# Motor_Measure.net
KiCad netlist of a schematic drawn in Altium Designer
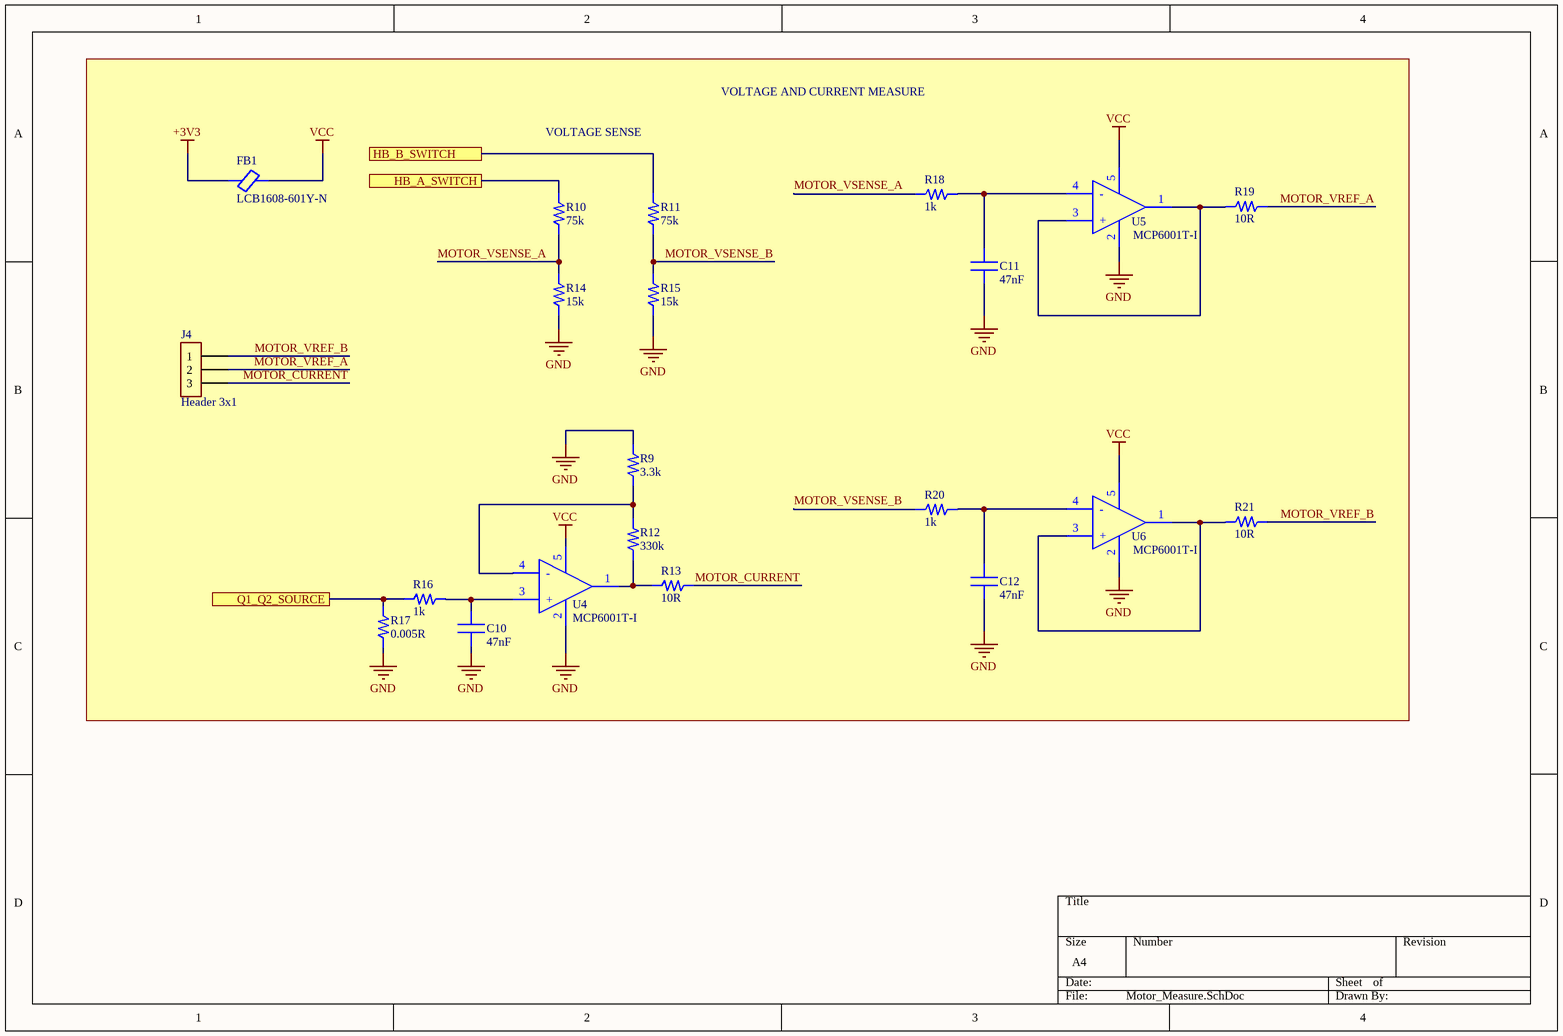
[diagram p0: Motor_Measure.SchDoc]

(export (version "E")
  (design (tool "Eeschema 10.0.6"))
  (components
    (comp (ref "C10")
      (value "47nF")
      (footprint "CAPC2012X145N 0805")
      (description "CL21B473KBCNNNC")
      (fields (field (name "TOLERANCE") "±10 %") (field (name "MANUFACTURER") "SAMSUNG"))
      (libsource (lib "Chicken_Coop_Door_Main_Board_V3") (part "CAP 0805 47nF CL21B473KBCNNNC"))
    )
    (comp (ref "C11")
      (value "47nF")
      (footprint "CAPC2012X145N 0805")
      (description "CL21B473KBCNNNC")
      (fields (field (name "TOLERANCE") "±10 %") (field (name "MANUFACTURER") "SAMSUNG"))
      (libsource (lib "Chicken_Coop_Door_Main_Board_V3") (part "CAP 0805 47nF CL21B473KBCNNNC"))
    )
    (comp (ref "C12")
      (value "47nF")
      (footprint "CAPC2012X145N 0805")
      (description "CL21B473KBCNNNC")
      (fields (field (name "TOLERANCE") "±10 %") (field (name "MANUFACTURER") "SAMSUNG"))
      (libsource (lib "Chicken_Coop_Door_Main_Board_V3") (part "CAP 0805 47nF CL21B473KBCNNNC"))
    )
    (comp (ref "FB1")
      (value "LCB1608-601Y-N")
      (footprint "MPZ1608S601ATA00 0603 1608X95N")
      (description "600 Ohms @ 100 MHz 1 Power Line Ferrite Bead 0603 (1608 Metric) 1A 200mOhm")
      (fields (field (name "TOLERANCE") "±25 %") (field (name "MANUFACTURER") "CORE MASTER"))
      (libsource (lib "Chicken_Coop_Door_Main_Board_V3") (part "Ferrite Bead LCB1608-601Y-N"))
    )
    (comp (ref "J4")
      (value "Header 3x1")
      (footprint "JST_B3B-PH-K-S 1x3 Header")
      (description "CON.T.B.2.00MM 3P 180C MALE CONNFLY")
      (fields (field (name "MANUFACTURER") "CONNFLY"))
      (libsource (lib "Chicken_Coop_Door_Main_Board_V3") (part "Header 3x1 DS1066-3MVW6X"))
    )
    (comp (ref "R9")
      (value "3.3k")
      (footprint "RES 0805 YAGEO C2012X60N")
      (description "RES.(2012) 0805 3.3K Ohms 1% 1/8W-S 100PPM")
      (fields (field (name "POWER") "1/8W") (field (name "TOLERANCE") "±1 %"))
      (libsource (lib "Chicken_Coop_Door_Main_Board_V3") (part "RES 0805 3.3k Ohms 0805S8F3301TDE"))
    )
    (comp (ref "R10")
      (value "75k")
      (footprint "RES 0805 YAGEO C2012X60N")
      (description "RES.(2012) 0805 75K Ohms 1% 1/8W-S 100PPM")
      (fields (field (name "POWER") "1/8W") (field (name "TOLERANCE") "±1 %"))
      (libsource (lib "Chicken_Coop_Door_Main_Board_V3") (part "RES 0805 75 kOhms 0805S8F7502T5E"))
    )
    (comp (ref "R11")
      (value "75k")
      (footprint "RES 0805 YAGEO C2012X60N")
      (description "RES.(2012) 0805 75K Ohms 1% 1/8W-S 100PPM")
      (fields (field (name "POWER") "1/8W") (field (name "TOLERANCE") "±1 %"))
      (libsource (lib "Chicken_Coop_Door_Main_Board_V3") (part "RES 0805 75 kOhms 0805S8F7502T5E"))
    )
    (comp (ref "R12")
      (value "330k")
      (footprint "RES 0603 ROYALOHM")
      (description "RES.(1608) 0603 330K Ohms 1% 1/10W-S 100PPM")
      (fields (field (name "TOLERANCE") "±5 %") (field (name "MANUFACTURER") "ROYALOHM"))
      (libsource (lib "Chicken_Coop_Door_Main_Board_V3") (part "RES 0603 330k 0603SAF3303T5E"))
    )
    (comp (ref "R13")
      (value "10R")
      (footprint "RES 0805 YAGEO C2012X60N")
      (description "RES.(2012) 0805 10 Ohms 5% 1/8W-S 400PPM")
      (fields (field (name "POWER") "1/8W") (field (name "TOLERANCE") "±1 %"))
      (libsource (lib "Chicken_Coop_Door_Main_Board_V3") (part "RES 0805 10 Ohms 0805S8J0100T5E"))
    )
    (comp (ref "R14")
      (value "15k")
      (footprint "RES 0805 YAGEO C2012X60N")
      (description "RES.(2012) 0805 15K Ohms 0.5% 1/8W 25PPM")
      (fields (field (name "POWER") "1/8W") (field (name "TOLERANCE") "±1 %"))
      (libsource (lib "Chicken_Coop_Door_Main_Board_V3") (part "RES 0805 15 kOhms TC0525D1502T5G"))
    )
    (comp (ref "R15")
      (value "15k")
      (footprint "RES 0805 YAGEO C2012X60N")
      (description "RES.(2012) 0805 15K Ohms 0.5% 1/8W 25PPM")
      (fields (field (name "POWER") "1/8W") (field (name "TOLERANCE") "±1 %"))
      (libsource (lib "Chicken_Coop_Door_Main_Board_V3") (part "RES 0805 15 kOhms TC0525D1502T5G"))
    )
    (comp (ref "R16")
      (value "1k")
      (footprint "RES 0805 YAGEO C2012X60N")
      (description "RES.(2012) 0805 1K Ohms 1% 1/8W-S 100PPM")
      (fields (field (name "POWER") "1/8W") (field (name "TOLERANCE") "±1 %"))
      (libsource (lib "Chicken_Coop_Door_Main_Board_V3") (part "RES 0805 1k Ohms 0805S8F1001TDE"))
    )
    (comp (ref "R17")
      (value "0.005R")
      (footprint "RES 1206 YAGEO")
      (description "RES.(3216) 1206 5m Ohms 1% 1/4W 100PPM AEC-Q200 SM")
      (fields (field (name "POWER") "1/4W") (field (name "TOLERANCE") "±1 %"))
      (libsource (lib "Chicken_Coop_Door_Main_Board_V3") (part "RES 1206 5 mOhms PE1206FRF070R005L"))
    )
    (comp (ref "R18")
      (value "1k")
      (footprint "RES 0805 YAGEO C2012X60N")
      (description "RES.(2012) 0805 1K Ohms 1% 1/8W-S 100PPM")
      (fields (field (name "POWER") "1/8W") (field (name "TOLERANCE") "±1 %"))
      (libsource (lib "Chicken_Coop_Door_Main_Board_V3") (part "RES 0805 1k Ohms 0805S8F1001TDE"))
    )
    (comp (ref "R19")
      (value "10R")
      (footprint "RES 0805 YAGEO C2012X60N")
      (description "RES.(2012) 0805 10 Ohms 5% 1/8W-S 400PPM")
      (fields (field (name "POWER") "1/8W") (field (name "TOLERANCE") "±1 %"))
      (libsource (lib "Chicken_Coop_Door_Main_Board_V3") (part "RES 0805 10 Ohms 0805S8J0100T5E"))
    )
    (comp (ref "R20")
      (value "1k")
      (footprint "RES 0805 YAGEO C2012X60N")
      (description "RES.(2012) 0805 1K Ohms 1% 1/8W-S 100PPM")
      (fields (field (name "POWER") "1/8W") (field (name "TOLERANCE") "±1 %"))
      (libsource (lib "Chicken_Coop_Door_Main_Board_V3") (part "RES 0805 1k Ohms 0805S8F1001TDE"))
    )
    (comp (ref "R21")
      (value "10R")
      (footprint "RES 0805 YAGEO C2012X60N")
      (description "RES.(2012) 0805 10 Ohms 5% 1/8W-S 400PPM")
      (fields (field (name "POWER") "1/8W") (field (name "TOLERANCE") "±1 %"))
      (libsource (lib "Chicken_Coop_Door_Main_Board_V3") (part "RES 0805 10 Ohms 0805S8J0100T5E"))
    )
    (comp (ref "U4")
      (value "MCP6001T-I")
      (footprint "MCP6001T-I/OT OPAMP SOT-23-5")
      (description "Standard (General Purpose) Amplifier 1 Circuit Rail-to-Rail SOT-23-5")
      (fields (field (name "MANUFACTURER") "Microchip Technology"))
      (libsource (lib "Chicken_Coop_Door_Main_Board_V3") (part "MCP6001T-I/OT OP-AMP 1 CH LOW POWER"))
    )
    (comp (ref "U5")
      (value "MCP6001T-I")
      (footprint "MCP6001T-I/OT OPAMP SOT-23-5")
      (description "Standard (General Purpose) Amplifier 1 Circuit Rail-to-Rail SOT-23-5")
      (fields (field (name "MANUFACTURER") "Microchip Technology"))
      (libsource (lib "Chicken_Coop_Door_Main_Board_V3") (part "MCP6001T-I/OT OP-AMP 1 CH LOW POWER"))
    )
    (comp (ref "U6")
      (value "MCP6001T-I")
      (footprint "MCP6001T-I/OT OPAMP SOT-23-5")
      (description "Standard (General Purpose) Amplifier 1 Circuit Rail-to-Rail SOT-23-5")
      (fields (field (name "MANUFACTURER") "Microchip Technology"))
      (libsource (lib "Chicken_Coop_Door_Main_Board_V3") (part "MCP6001T-I/OT OP-AMP 1 CH LOW POWER"))
    )
  )
  (nets
    (net (code "1") (name "+3V3") (class "Default")
      (node (ref "FB1") (pin "1") (pinfunction "1_1") (pintype "passive"))
    )
    (net (code "2") (name "/HB_A_SWITCH") (class "Default")
      (node (ref "R10") (pin "2") (pinfunction "2_2") (pintype "passive"))
    )
    (net (code "3") (name "/HB_B_SWITCH") (class "Default")
      (node (ref "R11") (pin "2") (pinfunction "2_2") (pintype "passive"))
    )
    (net (code "4") (name "/MOTOR_CURRENT") (class "Default")
      (node (ref "J4") (pin "3") (pinfunction "3_3") (pintype "passive"))
      (node (ref "R13") (pin "2") (pinfunction "2_2") (pintype "passive"))
    )
    (net (code "5") (name "/MOTOR_VREF_A") (class "Default")
      (node (ref "J4") (pin "2") (pinfunction "2_2") (pintype "passive"))
      (node (ref "R19") (pin "2") (pinfunction "2_2") (pintype "passive"))
    )
    (net (code "6") (name "/MOTOR_VREF_B") (class "Default")
      (node (ref "J4") (pin "1") (pinfunction "1_1") (pintype "passive"))
      (node (ref "R21") (pin "2") (pinfunction "2_2") (pintype "passive"))
    )
    (net (code "7") (name "/MOTOR_VSENSE_A") (class "Default")
      (node (ref "R10") (pin "1") (pinfunction "1_1") (pintype "passive"))
      (node (ref "R14") (pin "2") (pinfunction "2_2") (pintype "passive"))
      (node (ref "R18") (pin "1") (pinfunction "1_1") (pintype "passive"))
    )
    (net (code "8") (name "/MOTOR_VSENSE_B") (class "Default")
      (node (ref "R11") (pin "1") (pinfunction "1_1") (pintype "passive"))
      (node (ref "R15") (pin "2") (pinfunction "2_2") (pintype "passive"))
      (node (ref "R20") (pin "1") (pinfunction "1_1") (pintype "passive"))
    )
    (net (code "9") (name "/Q1_Q2_SOURCE") (class "Default")
      (node (ref "R16") (pin "1") (pinfunction "1_1") (pintype "passive"))
      (node (ref "R17") (pin "2") (pinfunction "2_2") (pintype "passive"))
    )
    (net (code "10") (name "GND") (class "Default")
      (node (ref "C10") (pin "1") (pinfunction "1_1") (pintype "passive"))
      (node (ref "C11") (pin "1") (pinfunction "1_1") (pintype "passive"))
      (node (ref "C12") (pin "1") (pinfunction "1_1") (pintype "passive"))
      (node (ref "R14") (pin "1") (pinfunction "1_1") (pintype "passive"))
      (node (ref "R15") (pin "1") (pinfunction "1_1") (pintype "passive"))
      (node (ref "R17") (pin "1") (pinfunction "1_1") (pintype "passive"))
      (node (ref "R9") (pin "2") (pinfunction "2_2") (pintype "passive"))
      (node (ref "U4") (pin "2") (pinfunction "VSS_2") (pintype "passive"))
      (node (ref "U5") (pin "2") (pinfunction "VSS_2") (pintype "passive"))
      (node (ref "U6") (pin "2") (pinfunction "VSS_2") (pintype "passive"))
    )
    (net (code "11") (name "Net-(U4-+)") (class "Default")
      (node (ref "C10") (pin "2") (pinfunction "2_2") (pintype "passive"))
      (node (ref "R16") (pin "2") (pinfunction "2_2") (pintype "passive"))
      (node (ref "U4") (pin "3") (pinfunction "+_3") (pintype "passive"))
    )
    (net (code "12") (name "Net-(U4--)") (class "Default")
      (node (ref "R12") (pin "2") (pinfunction "2_2") (pintype "passive"))
      (node (ref "R9") (pin "1") (pinfunction "1_1") (pintype "passive"))
      (node (ref "U4") (pin "4") (pinfunction "-_4") (pintype "passive"))
    )
    (net (code "13") (name "Net-(U4-Vout)") (class "Default")
      (node (ref "R12") (pin "1") (pinfunction "1_1") (pintype "passive"))
      (node (ref "R13") (pin "1") (pinfunction "1_1") (pintype "passive"))
      (node (ref "U4") (pin "1") (pinfunction "Vout_1") (pintype "passive"))
    )
    (net (code "14") (name "Net-(U5-+)") (class "Default")
      (node (ref "R19") (pin "1") (pinfunction "1_1") (pintype "passive"))
      (node (ref "U5") (pin "1") (pinfunction "Vout_1") (pintype "passive"))
      (node (ref "U5") (pin "3") (pinfunction "+_3") (pintype "passive"))
    )
    (net (code "15") (name "Net-(U5--)") (class "Default")
      (node (ref "C11") (pin "2") (pinfunction "2_2") (pintype "passive"))
      (node (ref "R18") (pin "2") (pinfunction "2_2") (pintype "passive"))
      (node (ref "U5") (pin "4") (pinfunction "-_4") (pintype "passive"))
    )
    (net (code "16") (name "Net-(U6-+)") (class "Default")
      (node (ref "R21") (pin "1") (pinfunction "1_1") (pintype "passive"))
      (node (ref "U6") (pin "1") (pinfunction "Vout_1") (pintype "passive"))
      (node (ref "U6") (pin "3") (pinfunction "+_3") (pintype "passive"))
    )
    (net (code "17") (name "Net-(U6--)") (class "Default")
      (node (ref "C12") (pin "2") (pinfunction "2_2") (pintype "passive"))
      (node (ref "R20") (pin "2") (pinfunction "2_2") (pintype "passive"))
      (node (ref "U6") (pin "4") (pinfunction "-_4") (pintype "passive"))
    )
    (net (code "18") (name "VCC") (class "Default")
      (node (ref "FB1") (pin "2") (pinfunction "2_2") (pintype "passive"))
      (node (ref "U4") (pin "5") (pinfunction "VDD_5") (pintype "passive"))
      (node (ref "U5") (pin "5") (pinfunction "VDD_5") (pintype "passive"))
      (node (ref "U6") (pin "5") (pinfunction "VDD_5") (pintype "passive"))
    )
  )
)
